# midi-breakout.net
KiCad netlist of a schematic drawn in EAGLE
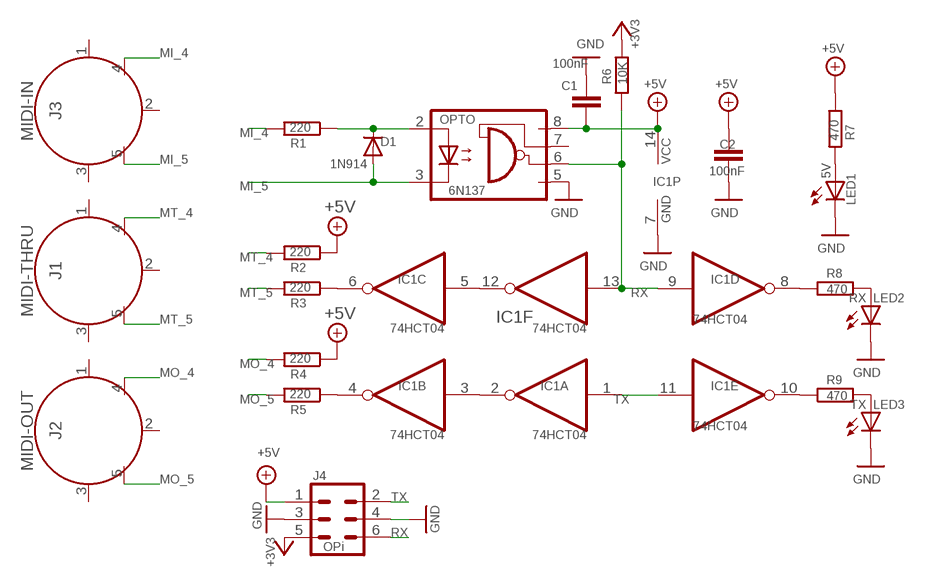
[diagram p0: schematic, sheet 1]

(export (version "E")
  (design (tool "Eeschema 10.0.6"))
  (components
    (comp (ref "C1")
      (value "100nF")
      (footprint "eagle-import:C050-024X044")
      (libsource (lib "eagle-import") (part "C-EU050-024X044"))
    )
    (comp (ref "C2")
      (value "100nF")
      (footprint "eagle-import:C050-024X044")
      (libsource (lib "eagle-import") (part "C-EU050-024X044"))
    )
    (comp (ref "D1")
      (value "1N914")
      (footprint "eagle-import:D-5")
      (libsource (lib "eagle-import") (part "DIODE-D-5"))
    )
    (comp (ref "IC1")
      (value "74HCT04")
      (footprint "eagle-import:DIL14")
      (libsource (lib "eagle-import") (part "7404NHCT"))
    )
    (comp (ref "J1")
      (value "MIDI-THRU")
      (footprint "eagle-import:DIN5-RA-PTH")
      (libsource (lib "eagle-import") (part "DIN5"))
    )
    (comp (ref "J2")
      (value "MIDI-OUT")
      (footprint "eagle-import:DIN5-RA-PTH")
      (libsource (lib "eagle-import") (part "DIN5"))
    )
    (comp (ref "J3")
      (value "MIDI-IN")
      (footprint "eagle-import:DIN5-RA-PTH")
      (libsource (lib "eagle-import") (part "DIN5"))
    )
    (comp (ref "J4")
      (value "OPi")
      (footprint "eagle-import:2X3-SHROUDED")
      (libsource (lib "eagle-import") (part "CONN_03X2SHROUD"))
    )
    (comp (ref "LED1")
      (value "5V")
      (footprint "eagle-import:LED3MM")
      (libsource (lib "eagle-import") (part "LED3MM"))
    )
    (comp (ref "LED2")
      (value "RX")
      (footprint "eagle-import:LED3MM")
      (libsource (lib "eagle-import") (part "LED3MM"))
    )
    (comp (ref "LED3")
      (value "TX")
      (footprint "eagle-import:LED3MM")
      (libsource (lib "eagle-import") (part "LED3MM"))
    )
    (comp (ref "OPTO")
      (value "6N137")
      (footprint "eagle-import:DIL08")
      (libsource (lib "eagle-import") (part "6N137"))
    )
    (comp (ref "R1")
      (value "220")
      (footprint "eagle-import:0204_5")
      (libsource (lib "eagle-import") (part "R-EU_0204/5"))
    )
    (comp (ref "R2")
      (value "220")
      (footprint "eagle-import:0204_5")
      (libsource (lib "eagle-import") (part "R-EU_0204/5"))
    )
    (comp (ref "R3")
      (value "220")
      (footprint "eagle-import:0204_5")
      (libsource (lib "eagle-import") (part "R-EU_0204/5"))
    )
    (comp (ref "R4")
      (value "220")
      (footprint "eagle-import:0204_5")
      (libsource (lib "eagle-import") (part "R-EU_0204/5"))
    )
    (comp (ref "R5")
      (value "220")
      (footprint "eagle-import:0204_5")
      (libsource (lib "eagle-import") (part "R-EU_0204/5"))
    )
    (comp (ref "R6")
      (value "10K")
      (footprint "eagle-import:0204_5")
      (libsource (lib "eagle-import") (part "R-EU_0204/5"))
    )
    (comp (ref "R7")
      (value "470")
      (footprint "eagle-import:0204_5")
      (libsource (lib "eagle-import") (part "R-EU_0204/5"))
    )
    (comp (ref "R8")
      (value "470")
      (footprint "eagle-import:0204_5")
      (libsource (lib "eagle-import") (part "R-EU_0204/5"))
    )
    (comp (ref "R9")
      (value "470")
      (footprint "eagle-import:0204_5")
      (libsource (lib "eagle-import") (part "R-EU_0204/5"))
    )
  )
  (nets
    (net (code "1") (name "+3V3") (class "Default")
      (node (ref "J4") (pin "5") (pinfunction "5_5") (pintype "bidirectional"))
      (node (ref "R6") (pin "2") (pinfunction "2_2") (pintype "passive"))
    )
    (net (code "2") (name "+5V") (class "Default")
      (node (ref "C1") (pin "2") (pinfunction "2_2") (pintype "passive"))
      (node (ref "C2") (pin "2") (pinfunction "2_2") (pintype "passive"))
      (node (ref "IC1") (pin "14") (pinfunction "VCC_14") (pintype "power_in"))
      (node (ref "J4") (pin "1") (pinfunction "1_1") (pintype "bidirectional"))
      (node (ref "OPTO") (pin "8") (pinfunction "VCC_8") (pintype "passive"))
      (node (ref "R2") (pin "1") (pinfunction "1_1") (pintype "passive"))
      (node (ref "R4") (pin "1") (pinfunction "1_1") (pintype "passive"))
      (node (ref "R7") (pin "1") (pinfunction "1_1") (pintype "passive"))
    )
    (net (code "3") (name "/MI_4") (class "Default")
      (node (ref "J3") (pin "4") (pinfunction "4_4") (pintype "bidirectional"))
      (node (ref "R1") (pin "2") (pinfunction "2_2") (pintype "passive"))
    )
    (net (code "4") (name "/MI_5") (class "Default")
      (node (ref "D1") (pin "A") (pinfunction "A_A") (pintype "passive"))
      (node (ref "J3") (pin "5") (pinfunction "5_5") (pintype "bidirectional"))
      (node (ref "OPTO") (pin "3") (pinfunction "C_3") (pintype "passive"))
    )
    (net (code "5") (name "/MO_4") (class "Default")
      (node (ref "J2") (pin "4") (pinfunction "4_4") (pintype "bidirectional"))
      (node (ref "R4") (pin "2") (pinfunction "2_2") (pintype "passive"))
    )
    (net (code "6") (name "/MO_5") (class "Default")
      (node (ref "J2") (pin "5") (pinfunction "5_5") (pintype "bidirectional"))
      (node (ref "R5") (pin "2") (pinfunction "2_2") (pintype "passive"))
    )
    (net (code "7") (name "/MT_4") (class "Default")
      (node (ref "J1") (pin "4") (pinfunction "4_4") (pintype "bidirectional"))
      (node (ref "R2") (pin "2") (pinfunction "2_2") (pintype "passive"))
    )
    (net (code "8") (name "/MT_5") (class "Default")
      (node (ref "J1") (pin "5") (pinfunction "5_5") (pintype "bidirectional"))
      (node (ref "R3") (pin "2") (pinfunction "2_2") (pintype "passive"))
    )
    (net (code "9") (name "/RX") (class "Default")
      (node (ref "IC1") (pin "13") (pinfunction "I_13") (pintype "input"))
      (node (ref "IC1") (pin "9") (pinfunction "I_9") (pintype "input"))
      (node (ref "J4") (pin "6") (pinfunction "6_6") (pintype "bidirectional"))
      (node (ref "OPTO") (pin "6") (pinfunction "VO_6") (pintype "passive"))
      (node (ref "R6") (pin "1") (pinfunction "1_1") (pintype "passive"))
    )
    (net (code "10") (name "/TX") (class "Default")
      (node (ref "IC1") (pin "1") (pinfunction "I_1") (pintype "input"))
      (node (ref "IC1") (pin "11") (pinfunction "I_11") (pintype "input"))
      (node (ref "J4") (pin "2") (pinfunction "2_2") (pintype "bidirectional"))
    )
    (net (code "11") (name "GND") (class "Default")
      (node (ref "C1") (pin "1") (pinfunction "1_1") (pintype "passive"))
      (node (ref "C2") (pin "1") (pinfunction "1_1") (pintype "passive"))
      (node (ref "IC1") (pin "7") (pinfunction "GND_7") (pintype "power_in"))
      (node (ref "J4") (pin "3") (pinfunction "3_3") (pintype "bidirectional"))
      (node (ref "J4") (pin "4") (pinfunction "4_4") (pintype "bidirectional"))
      (node (ref "LED1") (pin "K") (pinfunction "C_K") (pintype "passive"))
      (node (ref "LED2") (pin "K") (pinfunction "C_K") (pintype "passive"))
      (node (ref "LED3") (pin "K") (pinfunction "C_K") (pintype "passive"))
      (node (ref "OPTO") (pin "5") (pinfunction "GND_5") (pintype "passive"))
    )
    (net (code "12") (name "Net-(IC1A-O)") (class "Default")
      (node (ref "IC1") (pin "2") (pinfunction "O_2") (pintype "output"))
      (node (ref "IC1") (pin "3") (pinfunction "I_3") (pintype "input"))
    )
    (net (code "13") (name "Net-(IC1B-O)") (class "Default")
      (node (ref "IC1") (pin "4") (pinfunction "O_4") (pintype "output"))
      (node (ref "R5") (pin "1") (pinfunction "1_1") (pintype "passive"))
    )
    (net (code "14") (name "Net-(IC1C-I)") (class "Default")
      (node (ref "IC1") (pin "12") (pinfunction "O_12") (pintype "output"))
      (node (ref "IC1") (pin "5") (pinfunction "I_5") (pintype "input"))
    )
    (net (code "15") (name "Net-(IC1C-O)") (class "Default")
      (node (ref "IC1") (pin "6") (pinfunction "O_6") (pintype "output"))
      (node (ref "R3") (pin "1") (pinfunction "1_1") (pintype "passive"))
    )
    (net (code "16") (name "Net-(IC1D-O)") (class "Default")
      (node (ref "IC1") (pin "8") (pinfunction "O_8") (pintype "output"))
      (node (ref "R8") (pin "1") (pinfunction "1_1") (pintype "passive"))
    )
    (net (code "17") (name "Net-(IC1E-O)") (class "Default")
      (node (ref "IC1") (pin "10") (pinfunction "O_10") (pintype "output"))
      (node (ref "R9") (pin "1") (pinfunction "1_1") (pintype "passive"))
    )
    (net (code "18") (name "Net-(LED1-PadA)") (class "Default")
      (node (ref "LED1") (pin "A") (pinfunction "A_A") (pintype "passive"))
      (node (ref "R7") (pin "2") (pinfunction "2_2") (pintype "passive"))
    )
    (net (code "19") (name "Net-(LED2-PadA)") (class "Default")
      (node (ref "LED2") (pin "A") (pinfunction "A_A") (pintype "passive"))
      (node (ref "R8") (pin "2") (pinfunction "2_2") (pintype "passive"))
    )
    (net (code "20") (name "Net-(LED3-PadA)") (class "Default")
      (node (ref "LED3") (pin "A") (pinfunction "A_A") (pintype "passive"))
      (node (ref "R9") (pin "2") (pinfunction "2_2") (pintype "passive"))
    )
    (net (code "21") (name "Net-(OPTO-A)") (class "Default")
      (node (ref "D1") (pin "C") (pinfunction "C_C") (pintype "passive"))
      (node (ref "OPTO") (pin "2") (pinfunction "A_2") (pintype "passive"))
      (node (ref "R1") (pin "1") (pinfunction "1_1") (pintype "passive"))
    )
    (net (code "22") (name "unconnected-(J1-Pad1)") (class "Default")
      (node (ref "J1") (pin "1") (pinfunction "1_1") (pintype "bidirectional"))
    )
    (net (code "23") (name "unconnected-(J1-Pad2)") (class "Default")
      (node (ref "J1") (pin "2") (pinfunction "2_2") (pintype "bidirectional"))
    )
    (net (code "24") (name "unconnected-(J1-Pad3)") (class "Default")
      (node (ref "J1") (pin "3") (pinfunction "3_3") (pintype "bidirectional"))
    )
    (net (code "25") (name "unconnected-(J2-Pad1)") (class "Default")
      (node (ref "J2") (pin "1") (pinfunction "1_1") (pintype "bidirectional"))
    )
    (net (code "26") (name "unconnected-(J2-Pad2)") (class "Default")
      (node (ref "J2") (pin "2") (pinfunction "2_2") (pintype "bidirectional"))
    )
    (net (code "27") (name "unconnected-(J2-Pad3)") (class "Default")
      (node (ref "J2") (pin "3") (pinfunction "3_3") (pintype "bidirectional"))
    )
    (net (code "28") (name "unconnected-(J3-Pad1)") (class "Default")
      (node (ref "J3") (pin "1") (pinfunction "1_1") (pintype "bidirectional"))
    )
    (net (code "29") (name "unconnected-(J3-Pad2)") (class "Default")
      (node (ref "J3") (pin "2") (pinfunction "2_2") (pintype "bidirectional"))
    )
    (net (code "30") (name "unconnected-(J3-Pad3)") (class "Default")
      (node (ref "J3") (pin "3") (pinfunction "3_3") (pintype "bidirectional"))
    )
    (net (code "31") (name "unconnected-(OPTO-VE-Pad7)") (class "Default")
      (node (ref "OPTO") (pin "7") (pinfunction "VE_7") (pintype "passive"))
    )
  )
)
